# CANBUS.net
KiCad netlist of a schematic drawn in Altium Designer
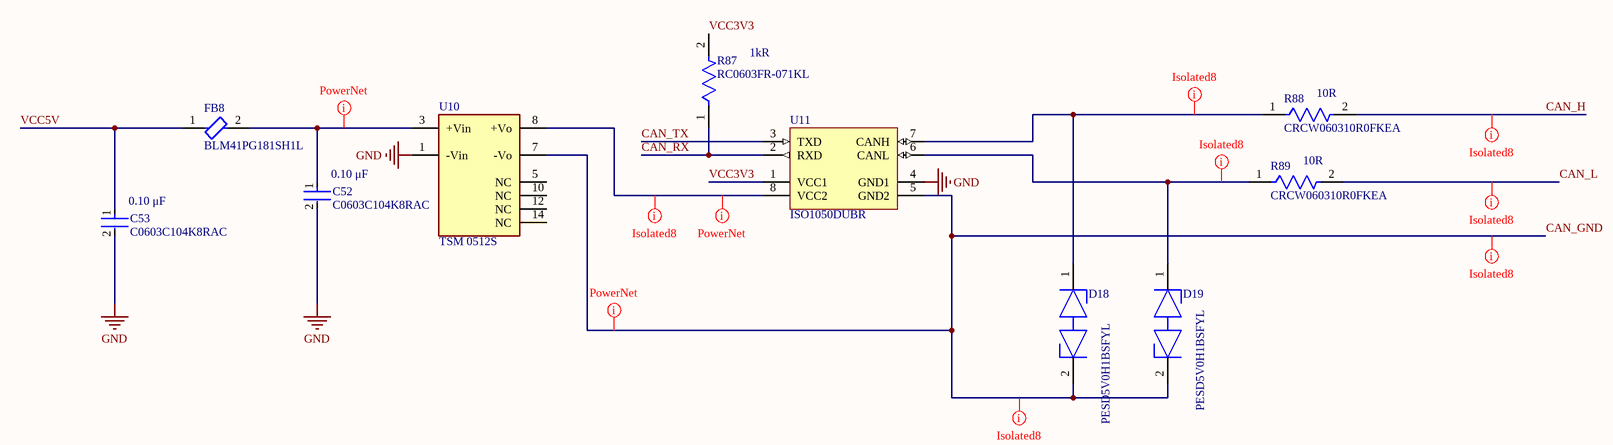
[diagram p0: CANBUS.SchDoc]

(export (version "E")
  (design (tool "Eeschema 10.0.6"))
  (components
    (comp (ref "C52")
      (value "C0603C104K8RAC")
      (footprint "FP-C0603C-CF-MFG")
      (description "C0603 0.10 μF X7R 30ppm/°C 10.00% 10 V")
      (fields
        (field (name "MANUFACTURER") "KEMET")
        (field (name "CAPACITANCE") "0.10 μF")
        (field (name "OCTOPART") "https://octopart.com/c0603c104k8rac-kemet-1325403")
      )
      (libsource (lib "Altium Content Vault") (part "b4654b650e69147ec39a6b967a45e02"))
    )
    (comp (ref "C53")
      (value "C0603C104K8RAC")
      (footprint "FP-C0603C-CF-MFG")
      (description "C0603 0.10 μF X7R 30ppm/°C 10.00% 10 V")
      (fields
        (field (name "MANUFACTURER") "KEMET")
        (field (name "CAPACITANCE") "0.10 μF")
        (field (name "OCTOPART") "https://octopart.com/c0603c104k8rac-kemet-1325403")
      )
      (libsource (lib "Altium Content Vault") (part "b4654b650e69147ec39a6b967a45e02"))
    )
    (comp (ref "D18")
      (value "PESD5V0H1BSFYL")
      (footprint "FP-SOD962-2-MFG")
      (description "TVS DIODE 5V 5V DSN0603-2")
      (fields
        (field (name "OCTOPART") "https://octopart.com/pesd5v0h1bsfyl-nexperia-78741149")
        (field (name "MANUFACTURER") "Nexperia")
      )
      (libsource (lib "Altium Content Vault") (part "35d3c4067516f6c39e60198d779250f"))
    )
    (comp (ref "D19")
      (value "PESD5V0H1BSFYL")
      (footprint "FP-SOD962-2-MFG")
      (description "TVS DIODE 5V 5V DSN0603-2")
      (fields
        (field (name "OCTOPART") "https://octopart.com/pesd5v0h1bsfyl-nexperia-78741149")
        (field (name "MANUFACTURER") "Nexperia")
      )
      (libsource (lib "Altium Content Vault") (part "35d3c4067516f6c39e60198d779250f"))
    )
    (comp (ref "FB8")
      (value "BLM41PG181SH1L")
      (footprint "FP-BLM41-0_2-a1_2-MFG")
      (description "Ferrite Bead, 1806, 180Ω @ 100MHz, 25%, 0.02Ω, 3.5A")
      (fields (field (name "TOLERANCE") "25%"))
      (libsource (lib "Altium Content Vault") (part "5f30dd21d616792df468990f7003faa"))
    )
    (comp (ref "R87")
      (value "RC0603FR-071KL")
      (footprint "FP-RC0603-0_55-IPC_C")
      (description "RES 1K OHM 1% 1/10W 0603")
      (fields (field (name "RESISTANCE") "1kR") (field (name "TOLERANCE") "1%"))
      (libsource (lib "Altium Content Vault") (part "1029c3af85768c4190bb7ad29bc67b5"))
    )
    (comp (ref "R88")
      (value "CRCW060310R0FKEA")
      (footprint "FP-CRCW0603-e3-IPC_A")
      (description "RES Thick Film, 10Ω, 1%, 0.1W, 100ppm/°C, 0603")
      (fields (field (name "RESISTANCE") "10R") (field (name "TOLERANCE") "1%"))
      (libsource (lib "Altium Content Vault") (part "1029c3af85768c4190bb7ad29bc67b5"))
    )
    (comp (ref "R89")
      (value "CRCW060310R0FKEA")
      (footprint "FP-CRCW0603-e3-IPC_A")
      (description "RES Thick Film, 10Ω, 1%, 0.1W, 100ppm/°C, 0603")
      (fields (field (name "RESISTANCE") "10R") (field (name "TOLERANCE") "1%"))
      (libsource (lib "Altium Content Vault") (part "1029c3af85768c4190bb7ad29bc67b5"))
    )
    (comp (ref "U10")
      (value "TSM 0512S")
      (footprint "FP-TSM_0512S-MFG")
      (description "DC DC CONVERTER 12V 960MW")
      (fields
        (field (name "OCTOPART") "https://octopart.com/tsm+0512s-tracopower-7394392")
        (field (name "MANUFACTURER") "Tracopower")
      )
      (libsource (lib "Altium Content Vault") (part "eabb76d147af65372c0c780fc4b7452"))
    )
    (comp (ref "U11")
      (value "ISO1050DUBR")
      (footprint "DUB0008A_L")
      (description "Isolated CAN Transceiver, -55 to 105 degC, 8-pin SOP (DUB), Green (RoHS & no Sb/Br)")
      (fields (field (name "MANUFACTURER") "Texas Instruments"))
      (libsource (lib "Altium Content Vault") (part "TI-ISO1050-SOP_DUB-8"))
    )
  )
  (nets
    (net (code "1") (name "/CAN_GND") (class "Default")
      (node (ref "D18") (pin "2") (pinfunction "K2_2") (pintype "passive"))
      (node (ref "D19") (pin "2") (pinfunction "K2_2") (pintype "passive"))
      (node (ref "U10") (pin "7") (pinfunction "-Vo_7") (pintype "power_in"))
      (node (ref "U11") (pin "5") (pinfunction "GND2_5") (pintype "power_in"))
    )
    (net (code "2") (name "/CAN_H") (class "Default")
      (node (ref "R88") (pin "2") (pinfunction "2_2") (pintype "passive"))
    )
    (net (code "3") (name "/CAN_L") (class "Default")
      (node (ref "R89") (pin "2") (pinfunction "2_2") (pintype "passive"))
    )
    (net (code "4") (name "/CAN_RX") (class "Default")
      (node (ref "R87") (pin "1") (pinfunction "1_1") (pintype "passive"))
      (node (ref "U11") (pin "2") (pinfunction "RXD_2") (pintype "output"))
    )
    (net (code "5") (name "/CAN_TX") (class "Default")
      (node (ref "U11") (pin "3") (pinfunction "TXD_3") (pintype "input"))
    )
    (net (code "6") (name "/VCC3V3") (class "Default")
      (node (ref "R87") (pin "2") (pinfunction "2_2") (pintype "passive"))
      (node (ref "U11") (pin "1") (pinfunction "VCC1_1") (pintype "power_in"))
    )
    (net (code "7") (name "/VCC5V") (class "Default")
      (node (ref "C53") (pin "1") (pinfunction "1_1") (pintype "passive"))
      (node (ref "FB8") (pin "1") (pinfunction "1_1") (pintype "passive"))
    )
    (net (code "8") (name "GND") (class "Default")
      (node (ref "C52") (pin "2") (pinfunction "2_2") (pintype "passive"))
      (node (ref "C53") (pin "2") (pinfunction "2_2") (pintype "passive"))
      (node (ref "U10") (pin "1") (pinfunction "-Vin_1") (pintype "power_in"))
      (node (ref "U11") (pin "4") (pinfunction "GND1_4") (pintype "power_in"))
    )
    (net (code "9") (name "Net-(D18-K1)") (class "Default")
      (node (ref "D18") (pin "1") (pinfunction "K1_1") (pintype "passive"))
      (node (ref "R88") (pin "1") (pinfunction "1_1") (pintype "passive"))
      (node (ref "U11") (pin "7") (pinfunction "CANH_7") (pintype "bidirectional"))
    )
    (net (code "10") (name "Net-(D19-K1)") (class "Default")
      (node (ref "D19") (pin "1") (pinfunction "K1_1") (pintype "passive"))
      (node (ref "R89") (pin "1") (pinfunction "1_1") (pintype "passive"))
      (node (ref "U11") (pin "6") (pinfunction "CANL_6") (pintype "bidirectional"))
    )
    (net (code "11") (name "Net-(U10-+Vin)") (class "Default")
      (node (ref "C52") (pin "1") (pinfunction "1_1") (pintype "passive"))
      (node (ref "FB8") (pin "2") (pinfunction "2_2") (pintype "passive"))
      (node (ref "U10") (pin "3") (pinfunction "+Vin_3") (pintype "power_in"))
    )
    (net (code "12") (name "Net-(U10-+Vo)") (class "Default")
      (node (ref "U10") (pin "8") (pinfunction "+Vo_8") (pintype "power_in"))
      (node (ref "U11") (pin "8") (pinfunction "VCC2_8") (pintype "power_in"))
    )
    (net (code "13") (name "unconnected-(U10-NC-Pad5)") (class "Default")
      (node (ref "U10") (pin "5") (pinfunction "NC_5") (pintype "passive"))
    )
    (net (code "14") (name "unconnected-(U10-NC-Pad10)") (class "Default")
      (node (ref "U10") (pin "10") (pinfunction "NC_10") (pintype "passive"))
    )
    (net (code "15") (name "unconnected-(U10-NC-Pad12)") (class "Default")
      (node (ref "U10") (pin "12") (pinfunction "NC_12") (pintype "passive"))
    )
    (net (code "16") (name "unconnected-(U10-NC-Pad14)") (class "Default")
      (node (ref "U10") (pin "14") (pinfunction "NC_14") (pintype "passive"))
    )
  )
)
